# breakout.net
KiCad netlist of a schematic drawn in EAGLE
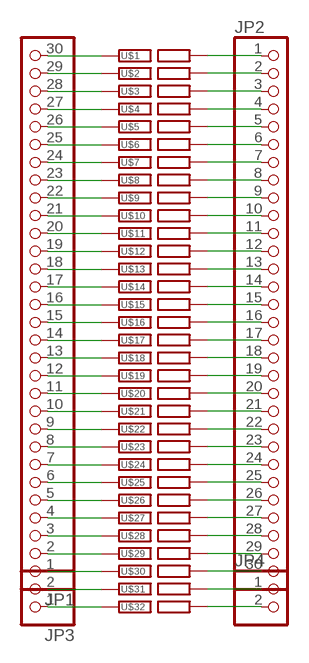
[diagram p0: schematic, sheet 1]

(export (version "E")
  (design (tool "Eeschema 10.0.6"))
  (components
    (comp (ref "JP1")
      (value "PINHD-1X30")
      (footprint "eagle-import:1X30")
      (libsource (lib "eagle-import") (part "PINHD-1X30"))
    )
    (comp (ref "JP2")
      (value "PINHD-1X30")
      (footprint "eagle-import:1X30")
      (libsource (lib "eagle-import") (part "PINHD-1X30"))
    )
    (comp (ref "JP3")
      (value "PINHD-1X2")
      (footprint "eagle-import:1X02")
      (libsource (lib "eagle-import") (part "PINHD-1X2"))
    )
    (comp (ref "JP4")
      (value "PINHD-1X2")
      (footprint "eagle-import:1X02")
      (libsource (lib "eagle-import") (part "PINHD-1X2"))
    )
    (comp (ref "U$1")
      (value "RAILSEP")
      (footprint "eagle-import:RAIL")
      (libsource (lib "eagle-import") (part "RAILSEP"))
    )
    (comp (ref "U$2")
      (value "RAILSEP")
      (footprint "eagle-import:RAIL")
      (libsource (lib "eagle-import") (part "RAILSEP"))
    )
    (comp (ref "U$3")
      (value "RAILSEP")
      (footprint "eagle-import:RAIL")
      (libsource (lib "eagle-import") (part "RAILSEP"))
    )
    (comp (ref "U$4")
      (value "RAILSEP")
      (footprint "eagle-import:RAIL")
      (libsource (lib "eagle-import") (part "RAILSEP"))
    )
    (comp (ref "U$5")
      (value "RAILSEP")
      (footprint "eagle-import:RAIL")
      (libsource (lib "eagle-import") (part "RAILSEP"))
    )
    (comp (ref "U$6")
      (value "RAILSEP")
      (footprint "eagle-import:RAIL")
      (libsource (lib "eagle-import") (part "RAILSEP"))
    )
    (comp (ref "U$7")
      (value "RAILSEP")
      (footprint "eagle-import:RAIL")
      (libsource (lib "eagle-import") (part "RAILSEP"))
    )
    (comp (ref "U$8")
      (value "RAILSEP")
      (footprint "eagle-import:RAIL")
      (libsource (lib "eagle-import") (part "RAILSEP"))
    )
    (comp (ref "U$9")
      (value "RAILSEP")
      (footprint "eagle-import:RAIL")
      (libsource (lib "eagle-import") (part "RAILSEP"))
    )
    (comp (ref "U$10")
      (value "RAILSEP")
      (footprint "eagle-import:RAIL")
      (libsource (lib "eagle-import") (part "RAILSEP"))
    )
    (comp (ref "U$11")
      (value "RAILSEP")
      (footprint "eagle-import:RAIL")
      (libsource (lib "eagle-import") (part "RAILSEP"))
    )
    (comp (ref "U$12")
      (value "RAILSEP")
      (footprint "eagle-import:RAIL")
      (libsource (lib "eagle-import") (part "RAILSEP"))
    )
    (comp (ref "U$13")
      (value "RAILSEP")
      (footprint "eagle-import:RAIL")
      (libsource (lib "eagle-import") (part "RAILSEP"))
    )
    (comp (ref "U$14")
      (value "RAILSEP")
      (footprint "eagle-import:RAIL")
      (libsource (lib "eagle-import") (part "RAILSEP"))
    )
    (comp (ref "U$15")
      (value "RAILSEP")
      (footprint "eagle-import:RAIL")
      (libsource (lib "eagle-import") (part "RAILSEP"))
    )
    (comp (ref "U$16")
      (value "RAILSEP")
      (footprint "eagle-import:RAIL")
      (libsource (lib "eagle-import") (part "RAILSEP"))
    )
    (comp (ref "U$17")
      (value "RAILSEP")
      (footprint "eagle-import:RAIL")
      (libsource (lib "eagle-import") (part "RAILSEP"))
    )
    (comp (ref "U$18")
      (value "RAILSEP")
      (footprint "eagle-import:RAIL")
      (libsource (lib "eagle-import") (part "RAILSEP"))
    )
    (comp (ref "U$19")
      (value "RAILSEP")
      (footprint "eagle-import:RAIL")
      (libsource (lib "eagle-import") (part "RAILSEP"))
    )
    (comp (ref "U$20")
      (value "RAILSEP")
      (footprint "eagle-import:RAIL")
      (libsource (lib "eagle-import") (part "RAILSEP"))
    )
    (comp (ref "U$21")
      (value "RAILSEP")
      (footprint "eagle-import:RAIL")
      (libsource (lib "eagle-import") (part "RAILSEP"))
    )
    (comp (ref "U$22")
      (value "RAILSEP")
      (footprint "eagle-import:RAIL")
      (libsource (lib "eagle-import") (part "RAILSEP"))
    )
    (comp (ref "U$23")
      (value "RAILSEP")
      (footprint "eagle-import:RAIL")
      (libsource (lib "eagle-import") (part "RAILSEP"))
    )
    (comp (ref "U$24")
      (value "RAILSEP")
      (footprint "eagle-import:RAIL")
      (libsource (lib "eagle-import") (part "RAILSEP"))
    )
    (comp (ref "U$25")
      (value "RAILSEP")
      (footprint "eagle-import:RAIL")
      (libsource (lib "eagle-import") (part "RAILSEP"))
    )
    (comp (ref "U$26")
      (value "RAILSEP")
      (footprint "eagle-import:RAIL")
      (libsource (lib "eagle-import") (part "RAILSEP"))
    )
    (comp (ref "U$27")
      (value "RAILSEP")
      (footprint "eagle-import:RAIL")
      (libsource (lib "eagle-import") (part "RAILSEP"))
    )
    (comp (ref "U$28")
      (value "RAILSEP")
      (footprint "eagle-import:RAIL")
      (libsource (lib "eagle-import") (part "RAILSEP"))
    )
    (comp (ref "U$29")
      (value "RAILSEP")
      (footprint "eagle-import:RAIL")
      (libsource (lib "eagle-import") (part "RAILSEP"))
    )
    (comp (ref "U$30")
      (value "RAILSEP")
      (footprint "eagle-import:RAIL")
      (libsource (lib "eagle-import") (part "RAILSEP"))
    )
    (comp (ref "U$31")
      (value "RAILSEP")
      (footprint "eagle-import:RAIL")
      (libsource (lib "eagle-import") (part "RAILSEP"))
    )
    (comp (ref "U$32")
      (value "RAILSEP")
      (footprint "eagle-import:RAIL")
      (libsource (lib "eagle-import") (part "RAILSEP"))
    )
  )
  (nets
    (net (code "1") (name "Net-(U$1-L)") (class "Default")
      (node (ref "JP1") (pin "30") (pinfunction "30_30") (pintype "passive"))
      (node (ref "U$1") (pin "P$L") (pinfunction "L_P$L") (pintype "bidirectional"))
    )
    (net (code "2") (name "Net-(U$1-R)") (class "Default")
      (node (ref "JP2") (pin "1") (pinfunction "1_1") (pintype "passive"))
      (node (ref "U$1") (pin "P$R") (pinfunction "R_P$R") (pintype "bidirectional"))
    )
    (net (code "3") (name "Net-(U$2-L)") (class "Default")
      (node (ref "JP1") (pin "29") (pinfunction "29_29") (pintype "passive"))
      (node (ref "U$2") (pin "P$L") (pinfunction "L_P$L") (pintype "bidirectional"))
    )
    (net (code "4") (name "Net-(U$2-R)") (class "Default")
      (node (ref "JP2") (pin "2") (pinfunction "2_2") (pintype "passive"))
      (node (ref "U$2") (pin "P$R") (pinfunction "R_P$R") (pintype "bidirectional"))
    )
    (net (code "5") (name "Net-(U$3-L)") (class "Default")
      (node (ref "JP1") (pin "28") (pinfunction "28_28") (pintype "passive"))
      (node (ref "U$3") (pin "P$L") (pinfunction "L_P$L") (pintype "bidirectional"))
    )
    (net (code "6") (name "Net-(U$3-R)") (class "Default")
      (node (ref "JP2") (pin "3") (pinfunction "3_3") (pintype "passive"))
      (node (ref "U$3") (pin "P$R") (pinfunction "R_P$R") (pintype "bidirectional"))
    )
    (net (code "7") (name "Net-(U$4-L)") (class "Default")
      (node (ref "JP1") (pin "27") (pinfunction "27_27") (pintype "passive"))
      (node (ref "U$4") (pin "P$L") (pinfunction "L_P$L") (pintype "bidirectional"))
    )
    (net (code "8") (name "Net-(U$4-R)") (class "Default")
      (node (ref "JP2") (pin "4") (pinfunction "4_4") (pintype "passive"))
      (node (ref "U$4") (pin "P$R") (pinfunction "R_P$R") (pintype "bidirectional"))
    )
    (net (code "9") (name "Net-(U$5-L)") (class "Default")
      (node (ref "JP1") (pin "26") (pinfunction "26_26") (pintype "passive"))
      (node (ref "U$5") (pin "P$L") (pinfunction "L_P$L") (pintype "bidirectional"))
    )
    (net (code "10") (name "Net-(U$5-R)") (class "Default")
      (node (ref "JP2") (pin "5") (pinfunction "5_5") (pintype "passive"))
      (node (ref "U$5") (pin "P$R") (pinfunction "R_P$R") (pintype "bidirectional"))
    )
    (net (code "11") (name "Net-(U$6-L)") (class "Default")
      (node (ref "JP1") (pin "25") (pinfunction "25_25") (pintype "passive"))
      (node (ref "U$6") (pin "P$L") (pinfunction "L_P$L") (pintype "bidirectional"))
    )
    (net (code "12") (name "Net-(U$6-R)") (class "Default")
      (node (ref "JP2") (pin "6") (pinfunction "6_6") (pintype "passive"))
      (node (ref "U$6") (pin "P$R") (pinfunction "R_P$R") (pintype "bidirectional"))
    )
    (net (code "13") (name "Net-(U$7-L)") (class "Default")
      (node (ref "JP1") (pin "24") (pinfunction "24_24") (pintype "passive"))
      (node (ref "U$7") (pin "P$L") (pinfunction "L_P$L") (pintype "bidirectional"))
    )
    (net (code "14") (name "Net-(U$7-R)") (class "Default")
      (node (ref "JP2") (pin "7") (pinfunction "7_7") (pintype "passive"))
      (node (ref "U$7") (pin "P$R") (pinfunction "R_P$R") (pintype "bidirectional"))
    )
    (net (code "15") (name "Net-(U$8-L)") (class "Default")
      (node (ref "JP1") (pin "23") (pinfunction "23_23") (pintype "passive"))
      (node (ref "U$8") (pin "P$L") (pinfunction "L_P$L") (pintype "bidirectional"))
    )
    (net (code "16") (name "Net-(U$8-R)") (class "Default")
      (node (ref "JP2") (pin "8") (pinfunction "8_8") (pintype "passive"))
      (node (ref "U$8") (pin "P$R") (pinfunction "R_P$R") (pintype "bidirectional"))
    )
    (net (code "17") (name "Net-(U$9-L)") (class "Default")
      (node (ref "JP1") (pin "22") (pinfunction "22_22") (pintype "passive"))
      (node (ref "U$9") (pin "P$L") (pinfunction "L_P$L") (pintype "bidirectional"))
    )
    (net (code "18") (name "Net-(U$9-R)") (class "Default")
      (node (ref "JP2") (pin "9") (pinfunction "9_9") (pintype "passive"))
      (node (ref "U$9") (pin "P$R") (pinfunction "R_P$R") (pintype "bidirectional"))
    )
    (net (code "19") (name "Net-(U$10-L)") (class "Default")
      (node (ref "JP1") (pin "21") (pinfunction "21_21") (pintype "passive"))
      (node (ref "U$10") (pin "P$L") (pinfunction "L_P$L") (pintype "bidirectional"))
    )
    (net (code "20") (name "Net-(U$10-R)") (class "Default")
      (node (ref "JP2") (pin "10") (pinfunction "10_10") (pintype "passive"))
      (node (ref "U$10") (pin "P$R") (pinfunction "R_P$R") (pintype "bidirectional"))
    )
    (net (code "21") (name "Net-(U$11-L)") (class "Default")
      (node (ref "JP1") (pin "20") (pinfunction "20_20") (pintype "passive"))
      (node (ref "U$11") (pin "P$L") (pinfunction "L_P$L") (pintype "bidirectional"))
    )
    (net (code "22") (name "Net-(U$11-R)") (class "Default")
      (node (ref "JP2") (pin "11") (pinfunction "11_11") (pintype "passive"))
      (node (ref "U$11") (pin "P$R") (pinfunction "R_P$R") (pintype "bidirectional"))
    )
    (net (code "23") (name "Net-(U$12-L)") (class "Default")
      (node (ref "JP1") (pin "19") (pinfunction "19_19") (pintype "passive"))
      (node (ref "U$12") (pin "P$L") (pinfunction "L_P$L") (pintype "bidirectional"))
    )
    (net (code "24") (name "Net-(U$12-R)") (class "Default")
      (node (ref "JP2") (pin "12") (pinfunction "12_12") (pintype "passive"))
      (node (ref "U$12") (pin "P$R") (pinfunction "R_P$R") (pintype "bidirectional"))
    )
    (net (code "25") (name "Net-(U$13-L)") (class "Default")
      (node (ref "JP1") (pin "18") (pinfunction "18_18") (pintype "passive"))
      (node (ref "U$13") (pin "P$L") (pinfunction "L_P$L") (pintype "bidirectional"))
    )
    (net (code "26") (name "Net-(U$13-R)") (class "Default")
      (node (ref "JP2") (pin "13") (pinfunction "13_13") (pintype "passive"))
      (node (ref "U$13") (pin "P$R") (pinfunction "R_P$R") (pintype "bidirectional"))
    )
    (net (code "27") (name "Net-(U$14-L)") (class "Default")
      (node (ref "JP1") (pin "17") (pinfunction "17_17") (pintype "passive"))
      (node (ref "U$14") (pin "P$L") (pinfunction "L_P$L") (pintype "bidirectional"))
    )
    (net (code "28") (name "Net-(U$14-R)") (class "Default")
      (node (ref "JP2") (pin "14") (pinfunction "14_14") (pintype "passive"))
      (node (ref "U$14") (pin "P$R") (pinfunction "R_P$R") (pintype "bidirectional"))
    )
    (net (code "29") (name "Net-(U$15-L)") (class "Default")
      (node (ref "JP1") (pin "16") (pinfunction "16_16") (pintype "passive"))
      (node (ref "U$15") (pin "P$L") (pinfunction "L_P$L") (pintype "bidirectional"))
    )
    (net (code "30") (name "Net-(U$15-R)") (class "Default")
      (node (ref "JP2") (pin "15") (pinfunction "15_15") (pintype "passive"))
      (node (ref "U$15") (pin "P$R") (pinfunction "R_P$R") (pintype "bidirectional"))
    )
    (net (code "31") (name "Net-(U$16-L)") (class "Default")
      (node (ref "JP1") (pin "15") (pinfunction "15_15") (pintype "passive"))
      (node (ref "U$16") (pin "P$L") (pinfunction "L_P$L") (pintype "bidirectional"))
    )
    (net (code "32") (name "Net-(U$16-R)") (class "Default")
      (node (ref "JP2") (pin "16") (pinfunction "16_16") (pintype "passive"))
      (node (ref "U$16") (pin "P$R") (pinfunction "R_P$R") (pintype "bidirectional"))
    )
    (net (code "33") (name "Net-(U$17-L)") (class "Default")
      (node (ref "JP1") (pin "14") (pinfunction "14_14") (pintype "passive"))
      (node (ref "U$17") (pin "P$L") (pinfunction "L_P$L") (pintype "bidirectional"))
    )
    (net (code "34") (name "Net-(U$17-R)") (class "Default")
      (node (ref "JP2") (pin "17") (pinfunction "17_17") (pintype "passive"))
      (node (ref "U$17") (pin "P$R") (pinfunction "R_P$R") (pintype "bidirectional"))
    )
    (net (code "35") (name "Net-(U$18-L)") (class "Default")
      (node (ref "JP1") (pin "13") (pinfunction "13_13") (pintype "passive"))
      (node (ref "U$18") (pin "P$L") (pinfunction "L_P$L") (pintype "bidirectional"))
    )
    (net (code "36") (name "Net-(U$18-R)") (class "Default")
      (node (ref "JP2") (pin "18") (pinfunction "18_18") (pintype "passive"))
      (node (ref "U$18") (pin "P$R") (pinfunction "R_P$R") (pintype "bidirectional"))
    )
    (net (code "37") (name "Net-(U$19-L)") (class "Default")
      (node (ref "JP1") (pin "12") (pinfunction "12_12") (pintype "passive"))
      (node (ref "U$19") (pin "P$L") (pinfunction "L_P$L") (pintype "bidirectional"))
    )
    (net (code "38") (name "Net-(U$19-R)") (class "Default")
      (node (ref "JP2") (pin "19") (pinfunction "19_19") (pintype "passive"))
      (node (ref "U$19") (pin "P$R") (pinfunction "R_P$R") (pintype "bidirectional"))
    )
    (net (code "39") (name "Net-(U$20-L)") (class "Default")
      (node (ref "JP1") (pin "11") (pinfunction "11_11") (pintype "passive"))
      (node (ref "U$20") (pin "P$L") (pinfunction "L_P$L") (pintype "bidirectional"))
    )
    (net (code "40") (name "Net-(U$20-R)") (class "Default")
      (node (ref "JP2") (pin "20") (pinfunction "20_20") (pintype "passive"))
      (node (ref "U$20") (pin "P$R") (pinfunction "R_P$R") (pintype "bidirectional"))
    )
    (net (code "41") (name "Net-(U$21-L)") (class "Default")
      (node (ref "JP1") (pin "10") (pinfunction "10_10") (pintype "passive"))
      (node (ref "U$21") (pin "P$L") (pinfunction "L_P$L") (pintype "bidirectional"))
    )
    (net (code "42") (name "Net-(U$21-R)") (class "Default")
      (node (ref "JP2") (pin "21") (pinfunction "21_21") (pintype "passive"))
      (node (ref "U$21") (pin "P$R") (pinfunction "R_P$R") (pintype "bidirectional"))
    )
    (net (code "43") (name "Net-(U$22-L)") (class "Default")
      (node (ref "JP1") (pin "9") (pinfunction "9_9") (pintype "passive"))
      (node (ref "U$22") (pin "P$L") (pinfunction "L_P$L") (pintype "bidirectional"))
    )
    (net (code "44") (name "Net-(U$22-R)") (class "Default")
      (node (ref "JP2") (pin "22") (pinfunction "22_22") (pintype "passive"))
      (node (ref "U$22") (pin "P$R") (pinfunction "R_P$R") (pintype "bidirectional"))
    )
    (net (code "45") (name "Net-(U$23-L)") (class "Default")
      (node (ref "JP1") (pin "8") (pinfunction "8_8") (pintype "passive"))
      (node (ref "U$23") (pin "P$L") (pinfunction "L_P$L") (pintype "bidirectional"))
    )
    (net (code "46") (name "Net-(U$23-R)") (class "Default")
      (node (ref "JP2") (pin "23") (pinfunction "23_23") (pintype "passive"))
      (node (ref "U$23") (pin "P$R") (pinfunction "R_P$R") (pintype "bidirectional"))
    )
    (net (code "47") (name "Net-(U$24-L)") (class "Default")
      (node (ref "JP1") (pin "7") (pinfunction "7_7") (pintype "passive"))
      (node (ref "U$24") (pin "P$L") (pinfunction "L_P$L") (pintype "bidirectional"))
    )
    (net (code "48") (name "Net-(U$24-R)") (class "Default")
      (node (ref "JP2") (pin "24") (pinfunction "24_24") (pintype "passive"))
      (node (ref "U$24") (pin "P$R") (pinfunction "R_P$R") (pintype "bidirectional"))
    )
    (net (code "49") (name "Net-(U$25-L)") (class "Default")
      (node (ref "JP1") (pin "6") (pinfunction "6_6") (pintype "passive"))
      (node (ref "U$25") (pin "P$L") (pinfunction "L_P$L") (pintype "bidirectional"))
    )
    (net (code "50") (name "Net-(U$25-R)") (class "Default")
      (node (ref "JP2") (pin "25") (pinfunction "25_25") (pintype "passive"))
      (node (ref "U$25") (pin "P$R") (pinfunction "R_P$R") (pintype "bidirectional"))
    )
    (net (code "51") (name "Net-(U$26-L)") (class "Default")
      (node (ref "JP1") (pin "5") (pinfunction "5_5") (pintype "passive"))
      (node (ref "U$26") (pin "P$L") (pinfunction "L_P$L") (pintype "bidirectional"))
    )
    (net (code "52") (name "Net-(U$26-R)") (class "Default")
      (node (ref "JP2") (pin "26") (pinfunction "26_26") (pintype "passive"))
      (node (ref "U$26") (pin "P$R") (pinfunction "R_P$R") (pintype "bidirectional"))
    )
    (net (code "53") (name "Net-(U$27-L)") (class "Default")
      (node (ref "JP1") (pin "4") (pinfunction "4_4") (pintype "passive"))
      (node (ref "U$27") (pin "P$L") (pinfunction "L_P$L") (pintype "bidirectional"))
    )
    (net (code "54") (name "Net-(U$27-R)") (class "Default")
      (node (ref "JP2") (pin "27") (pinfunction "27_27") (pintype "passive"))
      (node (ref "U$27") (pin "P$R") (pinfunction "R_P$R") (pintype "bidirectional"))
    )
    (net (code "55") (name "Net-(U$28-L)") (class "Default")
      (node (ref "JP1") (pin "3") (pinfunction "3_3") (pintype "passive"))
      (node (ref "U$28") (pin "P$L") (pinfunction "L_P$L") (pintype "bidirectional"))
    )
    (net (code "56") (name "Net-(U$28-R)") (class "Default")
      (node (ref "JP2") (pin "28") (pinfunction "28_28") (pintype "passive"))
      (node (ref "U$28") (pin "P$R") (pinfunction "R_P$R") (pintype "bidirectional"))
    )
    (net (code "57") (name "Net-(U$29-L)") (class "Default")
      (node (ref "JP1") (pin "2") (pinfunction "2_2") (pintype "passive"))
      (node (ref "U$29") (pin "P$L") (pinfunction "L_P$L") (pintype "bidirectional"))
    )
    (net (code "58") (name "Net-(U$29-R)") (class "Default")
      (node (ref "JP2") (pin "29") (pinfunction "29_29") (pintype "passive"))
      (node (ref "U$29") (pin "P$R") (pinfunction "R_P$R") (pintype "bidirectional"))
    )
    (net (code "59") (name "Net-(U$30-L)") (class "Default")
      (node (ref "JP1") (pin "1") (pinfunction "1_1") (pintype "passive"))
      (node (ref "U$30") (pin "P$L") (pinfunction "L_P$L") (pintype "bidirectional"))
    )
    (net (code "60") (name "Net-(U$30-R)") (class "Default")
      (node (ref "JP2") (pin "30") (pinfunction "30_30") (pintype "passive"))
      (node (ref "U$30") (pin "P$R") (pinfunction "R_P$R") (pintype "bidirectional"))
    )
    (net (code "61") (name "Net-(U$31-L)") (class "Default")
      (node (ref "JP3") (pin "2") (pinfunction "2_2") (pintype "passive"))
      (node (ref "U$31") (pin "P$L") (pinfunction "L_P$L") (pintype "bidirectional"))
    )
    (net (code "62") (name "Net-(U$31-R)") (class "Default")
      (node (ref "JP4") (pin "1") (pinfunction "1_1") (pintype "passive"))
      (node (ref "U$31") (pin "P$R") (pinfunction "R_P$R") (pintype "bidirectional"))
    )
    (net (code "63") (name "Net-(U$32-L)") (class "Default")
      (node (ref "JP3") (pin "1") (pinfunction "1_1") (pintype "passive"))
      (node (ref "U$32") (pin "P$L") (pinfunction "L_P$L") (pintype "bidirectional"))
    )
    (net (code "64") (name "Net-(U$32-R)") (class "Default")
      (node (ref "JP4") (pin "2") (pinfunction "2_2") (pintype "passive"))
      (node (ref "U$32") (pin "P$R") (pinfunction "R_P$R") (pintype "bidirectional"))
    )
  )
)
